# SCH.net
KiCad netlist of a schematic drawn in Altium Designer
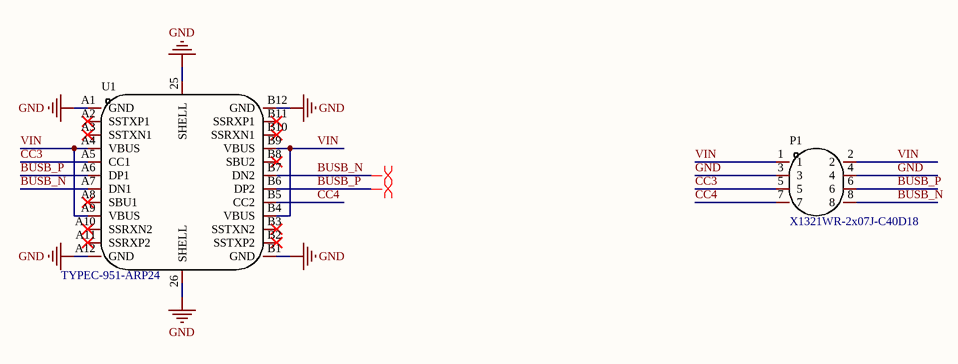
[diagram p0: SCH.SchDoc]

(export (version "E")
  (design (tool "Eeschema 10.0.6"))
  (components
    (comp (ref "P1")
      (value "X1321WR-2x07J-C40D18")
      (footprint "HDR-TH_8P-P1.27-L")
      (description "双排弯针2*4P")
      (fields (field (name "MANUFACTURER") "XKB Connectivity(中国星坤)"))
      (libsource (lib "DHO800_Battery_Pack_LED_V1.0") (part "双排插针"))
    )
    (comp (ref "U1")
      (value "TYPEC-951-ARP24")
      (footprint "USB-C-SMD_TYPEC-951-ARP24")
      (description "USB C公头")
      (fields (field (name "MANUFACTURER") "XUNPU(讯普)"))
      (libsource (lib "DHO800_Battery_Pack_IP5389_V1.0_2") (part "TYPEC-951-ARP24"))
    )
  )
  (nets
    (net (code "1") (name "/BUSB_N") (class "Default")
      (node (ref "P1") (pin "8") (pinfunction "8_8") (pintype "passive"))
      (node (ref "U1") (pin "A7") (pinfunction "DN1_A7") (pintype "passive"))
      (node (ref "U1") (pin "B7") (pinfunction "DN2_B7") (pintype "passive"))
    )
    (net (code "2") (name "/BUSB_P") (class "Default")
      (node (ref "P1") (pin "6") (pinfunction "6_6") (pintype "passive"))
      (node (ref "U1") (pin "A6") (pinfunction "DP1_A6") (pintype "passive"))
      (node (ref "U1") (pin "B6") (pinfunction "DP2_B6") (pintype "passive"))
    )
    (net (code "3") (name "/CC3") (class "Default")
      (node (ref "P1") (pin "5") (pinfunction "5_5") (pintype "passive"))
      (node (ref "U1") (pin "A5") (pinfunction "CC1_A5") (pintype "passive"))
    )
    (net (code "4") (name "/CC4") (class "Default")
      (node (ref "P1") (pin "7") (pinfunction "7_7") (pintype "passive"))
      (node (ref "U1") (pin "B5") (pinfunction "CC2_B5") (pintype "passive"))
    )
    (net (code "5") (name "/VIN") (class "Default")
      (node (ref "P1") (pin "1") (pinfunction "1_1") (pintype "passive"))
      (node (ref "P1") (pin "2") (pinfunction "2_2") (pintype "passive"))
      (node (ref "U1") (pin "A4") (pinfunction "VBUS_A4") (pintype "passive"))
      (node (ref "U1") (pin "A9") (pinfunction "VBUS_A9") (pintype "passive"))
      (node (ref "U1") (pin "B4") (pinfunction "VBUS_B4") (pintype "passive"))
      (node (ref "U1") (pin "B9") (pinfunction "VBUS_B9") (pintype "passive"))
    )
    (net (code "6") (name "GND") (class "Default")
      (node (ref "P1") (pin "3") (pinfunction "3_3") (pintype "passive"))
      (node (ref "P1") (pin "4") (pinfunction "4_4") (pintype "passive"))
      (node (ref "U1") (pin "25") (pinfunction "SHELL_25") (pintype "passive"))
      (node (ref "U1") (pin "26") (pinfunction "SHELL_26") (pintype "passive"))
      (node (ref "U1") (pin "A1") (pinfunction "GND_A1") (pintype "passive"))
      (node (ref "U1") (pin "A12") (pinfunction "GND_A12") (pintype "passive"))
      (node (ref "U1") (pin "B1") (pinfunction "GND_B1") (pintype "passive"))
      (node (ref "U1") (pin "B12") (pinfunction "GND_B12") (pintype "passive"))
    )
    (net (code "7") (name "unconnected-(U1-SBU1-PadA8)") (class "Default")
      (node (ref "U1") (pin "A8") (pinfunction "SBU1_A8") (pintype "passive+no_connect"))
    )
    (net (code "8") (name "unconnected-(U1-SBU2-PadB8)") (class "Default")
      (node (ref "U1") (pin "B8") (pinfunction "SBU2_B8") (pintype "passive+no_connect"))
    )
    (net (code "9") (name "unconnected-(U1-SSRXN1-PadB10)") (class "Default")
      (node (ref "U1") (pin "B10") (pinfunction "SSRXN1_B10") (pintype "passive+no_connect"))
    )
    (net (code "10") (name "unconnected-(U1-SSRXN2-PadA10)") (class "Default")
      (node (ref "U1") (pin "A10") (pinfunction "SSRXN2_A10") (pintype "passive+no_connect"))
    )
    (net (code "11") (name "unconnected-(U1-SSRXP1-PadB11)") (class "Default")
      (node (ref "U1") (pin "B11") (pinfunction "SSRXP1_B11") (pintype "passive+no_connect"))
    )
    (net (code "12") (name "unconnected-(U1-SSRXP2-PadA11)") (class "Default")
      (node (ref "U1") (pin "A11") (pinfunction "SSRXP2_A11") (pintype "passive+no_connect"))
    )
    (net (code "13") (name "unconnected-(U1-SSTXN1-PadA3)") (class "Default")
      (node (ref "U1") (pin "A3") (pinfunction "SSTXN1_A3") (pintype "passive+no_connect"))
    )
    (net (code "14") (name "unconnected-(U1-SSTXN2-PadB3)") (class "Default")
      (node (ref "U1") (pin "B3") (pinfunction "SSTXN2_B3") (pintype "passive+no_connect"))
    )
    (net (code "15") (name "unconnected-(U1-SSTXP1-PadA2)") (class "Default")
      (node (ref "U1") (pin "A2") (pinfunction "SSTXP1_A2") (pintype "passive+no_connect"))
    )
    (net (code "16") (name "unconnected-(U1-SSTXP2-PadB2)") (class "Default")
      (node (ref "U1") (pin "B2") (pinfunction "SSTXP2_B2") (pintype "passive+no_connect"))
    )
  )
)
